# 1-Schematic_Esp12F.net
KiCad netlist of a schematic drawn in EasyEDA
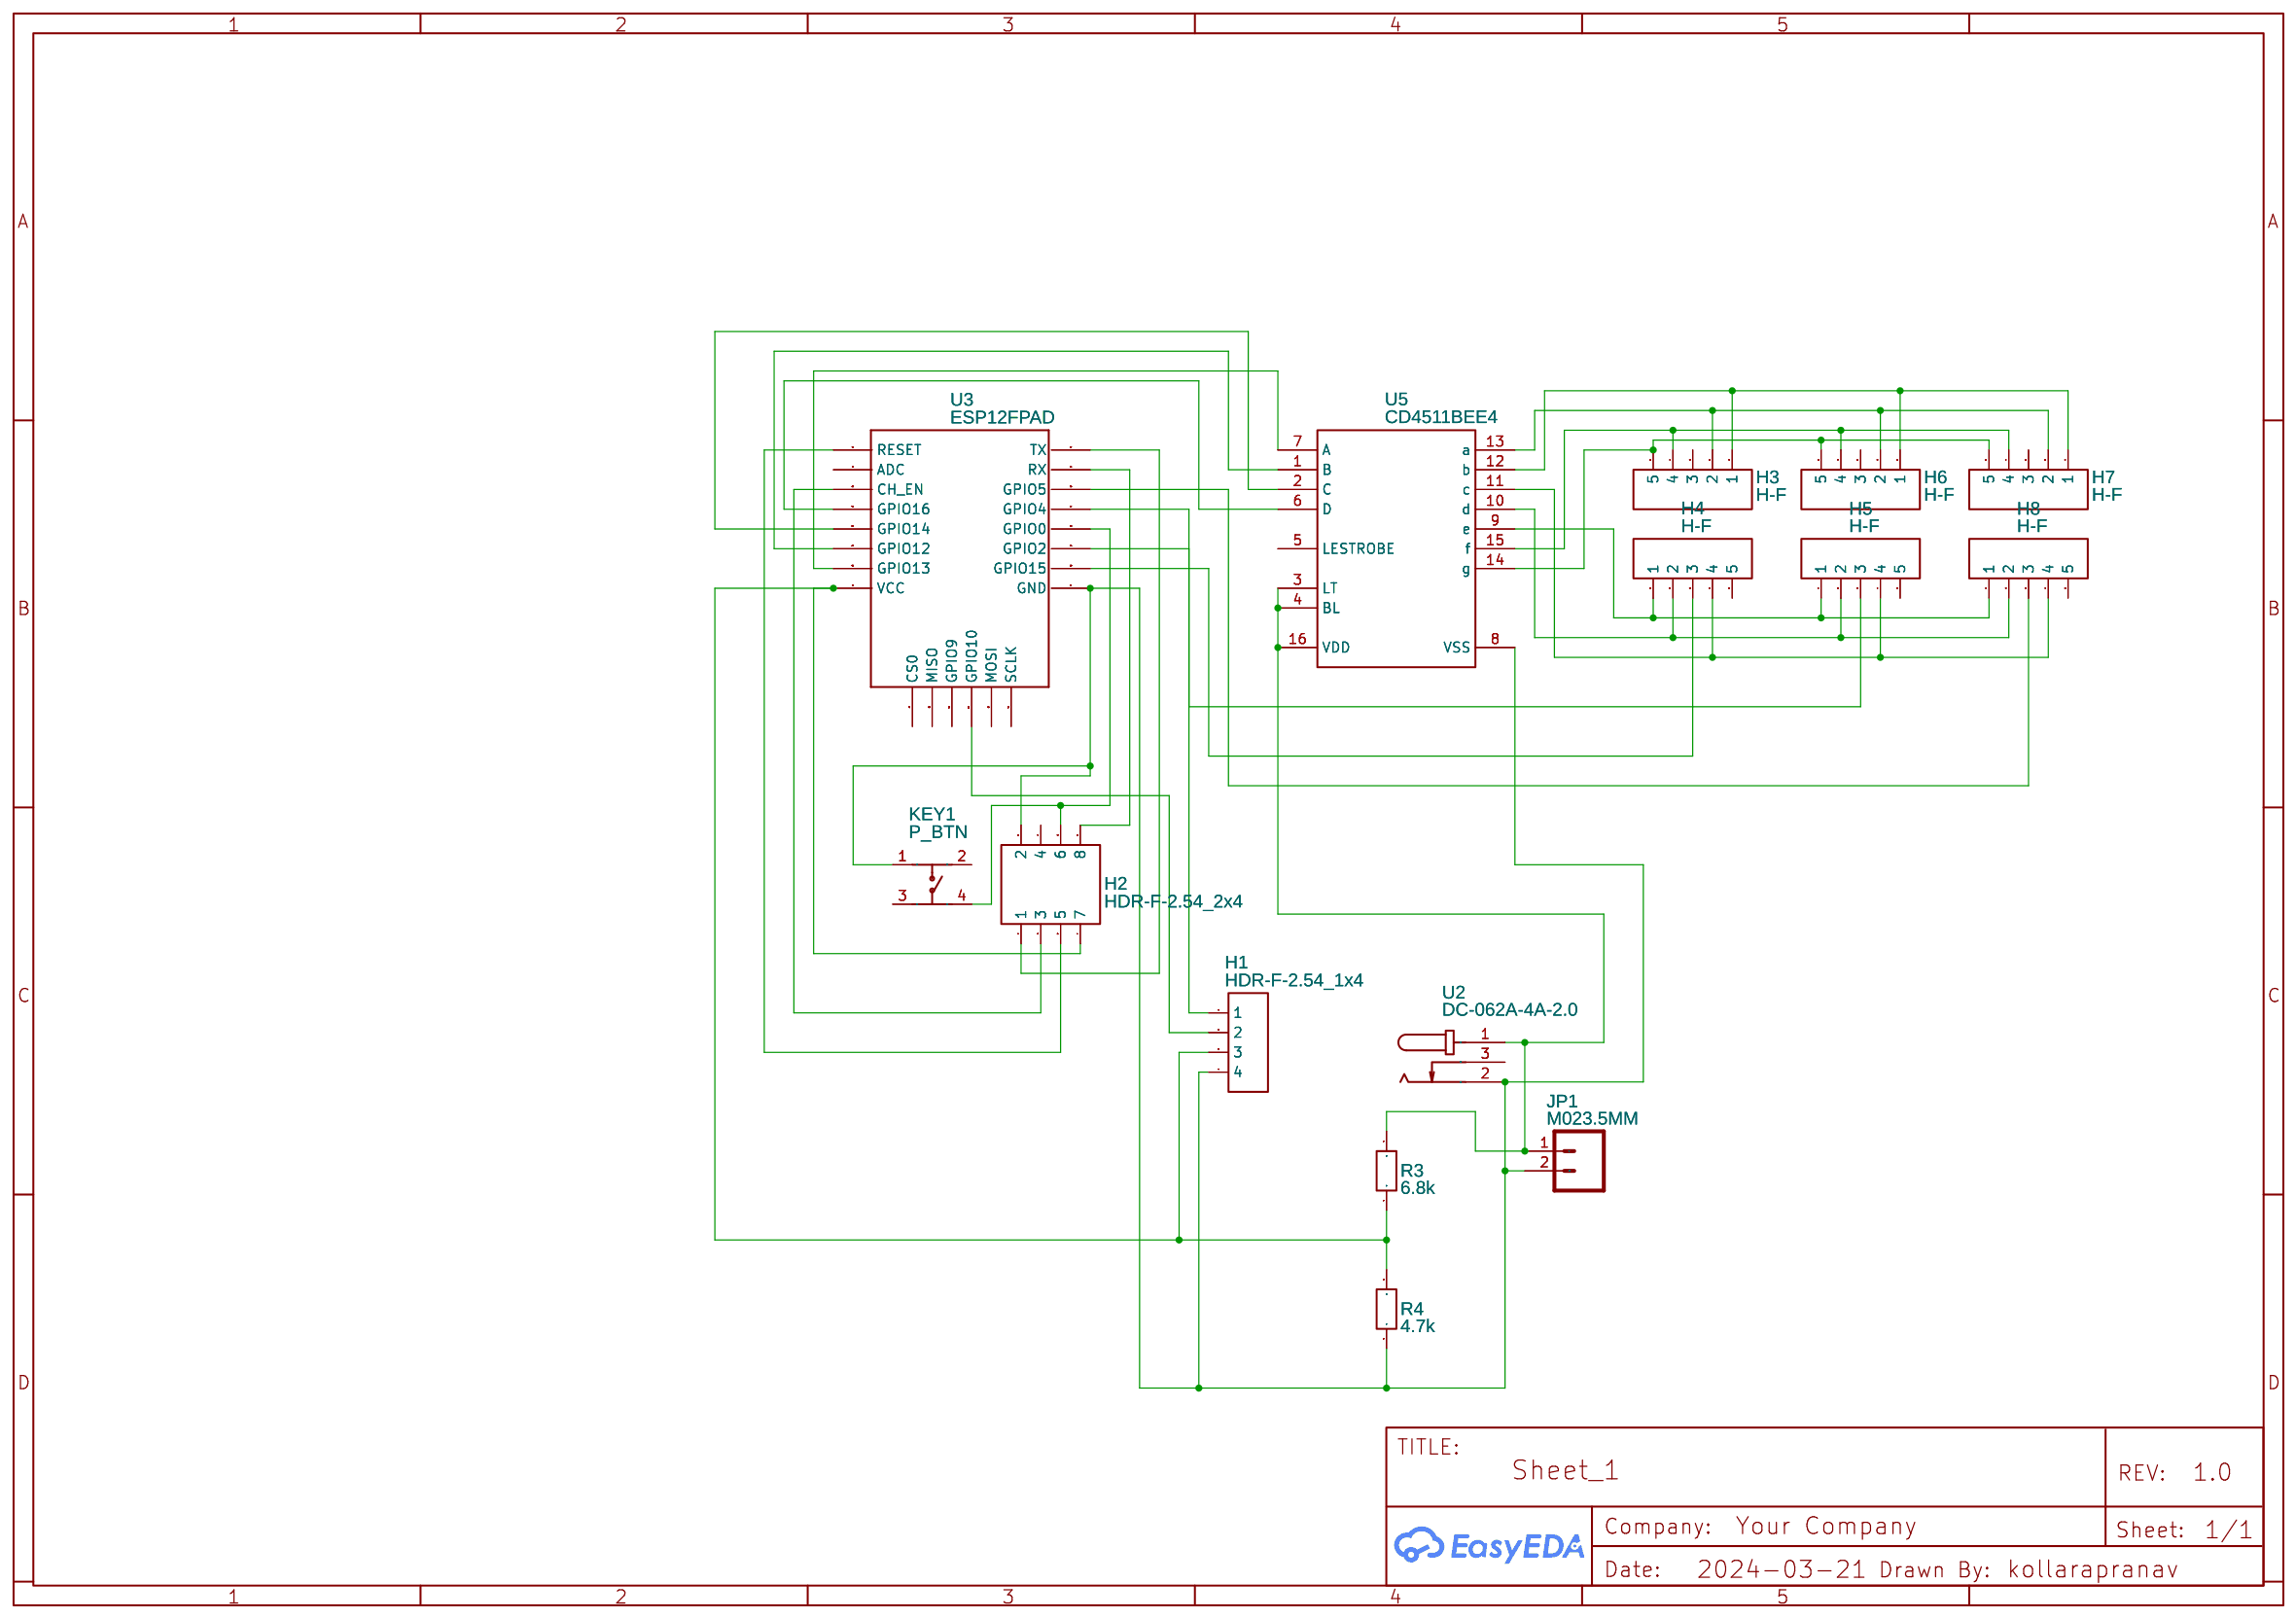
[diagram p0: schematic sheet]

(export (version "E")
  (design (tool "Eeschema 10.0.6"))
  (components
    (comp (ref "H1") (value "HDR-F-2.54_1x4") (libsource (lib "") (part "HDR-F-2.54_1x4")))
    (comp (ref "H2") (value "HDR-F-2.54_2x4") (libsource (lib "") (part "HDR-F-2.54_2x4")))
    (comp (ref "H3") (value "H-F") (libsource (lib "") (part "HDR-F-2.54_1x5")))
    (comp (ref "H4") (value "H-F") (libsource (lib "") (part "HDR-F-2.54_1x5_1")))
    (comp (ref "H5") (value "H-F") (libsource (lib "") (part "HDR-F-2.54_1x5_1")))
    (comp (ref "H6") (value "H-F") (libsource (lib "") (part "HDR-F-2.54_1x5")))
    (comp (ref "H7") (value "H-F") (libsource (lib "") (part "HDR-F-2.54_1x5")))
    (comp (ref "H8") (value "H-F") (libsource (lib "") (part "HDR-F-2.54_1x5_1")))
    (comp (ref "JP1") (value "M023.5MM") (libsource (lib "") (part "M023.5MM")))
    (comp (ref "KEY1")
      (value "P_BTN")
      (fields (field (name "Manufacturer Part") "4pinTACTPCBTHTPushButton"))
      (libsource (lib "") (part "4PINTACTPCBTHTPUSHBUTTON"))
    )
    (comp (ref "R3") (value "6.8k") (libsource (lib "") (part "Res_AXIAL-0.4(1/4W)_EU")))
    (comp (ref "R4") (value "4.7k") (libsource (lib "") (part "Res_AXIAL-0.4(1/4W)_EU")))
    (comp (ref "U2")
      (value "DC-062A-4A-2.0")
      (fields (field (name "Manufacturer") "XKB Connection(中国星坤)"))
      (libsource (lib "") (part "DC-062A-4A-2.0"))
    )
    (comp (ref "U3") (value "ESP12FPAD") (libsource (lib "") (part "ESP12FPAD")))
    (comp (ref "U5") (value "CD4511BEE4") (libsource (lib "") (part "CD4511BEE4")))
  )
  (nets
    (net (code "1") (name "Net-(H1-Pad1)") (class "Default")
      (node (ref "H1") (pin "1") (pinfunction "1_1") (pintype "unspecified"))
      (node (ref "U3") (pin "GPIO4") (pinfunction "GPIO4_GPIO4") (pintype "bidirectional"))
    )
    (net (code "2") (name "Net-(H1-Pad2)") (class "Default")
      (node (ref "H1") (pin "2") (pinfunction "2_2") (pintype "unspecified"))
      (node (ref "U3") (pin "GPIO10") (pinfunction "GPIO10_GPIO10") (pintype "bidirectional"))
    )
    (net (code "3") (name "Net-(H1-Pad3)") (class "Default")
      (node (ref "H1") (pin "3") (pinfunction "3_3") (pintype "unspecified"))
      (node (ref "H2") (pin "7") (pinfunction "7_7") (pintype "unspecified"))
      (node (ref "R3") (pin "1") (pinfunction "1_1") (pintype "unspecified"))
      (node (ref "R4") (pin "2") (pinfunction "2_2") (pintype "unspecified"))
      (node (ref "U3") (pin "VCC") (pinfunction "VCC_VCC") (pintype "bidirectional"))
    )
    (net (code "4") (name "Net-(H2-Pad5)") (class "Default")
      (node (ref "H2") (pin "5") (pinfunction "5_5") (pintype "unspecified"))
      (node (ref "U3") (pin "RESET") (pinfunction "RESET_RESET") (pintype "bidirectional"))
    )
    (net (code "5") (name "Net-(H2-Pad6)") (class "Default")
      (node (ref "H2") (pin "6") (pinfunction "6_6") (pintype "unspecified"))
      (node (ref "KEY1") (pin "4") (pinfunction "4_4") (pintype "unspecified"))
      (node (ref "U3") (pin "GPIO0") (pinfunction "GPIO0_GPIO0") (pintype "bidirectional"))
    )
    (net (code "6") (name "Net-(H4-Pad3)") (class "Default")
      (node (ref "H4") (pin "3") (pinfunction "3_3") (pintype "unspecified"))
      (node (ref "U3") (pin "GPIO15") (pinfunction "GPIO15_GPIO15") (pintype "bidirectional"))
    )
    (net (code "7") (name "Net-(H5-Pad3)") (class "Default")
      (node (ref "H5") (pin "3") (pinfunction "3_3") (pintype "unspecified"))
      (node (ref "U3") (pin "GPIO2") (pinfunction "GPIO2_GPIO2") (pintype "bidirectional"))
    )
    (net (code "8") (name "Net-(H8-Pad3)") (class "Default")
      (node (ref "H8") (pin "3") (pinfunction "3_3") (pintype "unspecified"))
      (node (ref "U3") (pin "GPIO5") (pinfunction "GPIO5_GPIO5") (pintype "bidirectional"))
    )
    (net (code "9") (name "Net-(U3-CH_EN)") (class "Default")
      (node (ref "H2") (pin "3") (pinfunction "3_3") (pintype "unspecified"))
      (node (ref "U3") (pin "CH_PD") (pinfunction "CH_EN_CH_PD") (pintype "bidirectional"))
    )
    (net (code "10") (name "Net-(U3-RX)") (class "Default")
      (node (ref "H2") (pin "8") (pinfunction "8_8") (pintype "unspecified"))
      (node (ref "U3") (pin "RXD0") (pinfunction "RX_RXD0") (pintype "bidirectional"))
    )
    (net (code "11") (name "Net-(U3-TX)") (class "Default")
      (node (ref "H2") (pin "1") (pinfunction "1_1") (pintype "unspecified"))
      (node (ref "U3") (pin "TXD0") (pinfunction "TX_TXD0") (pintype "bidirectional"))
    )
    (net (code "12") (name "Net-(U5-A)") (class "Default")
      (node (ref "U3") (pin "GPIO13") (pinfunction "GPIO13_GPIO13") (pintype "bidirectional"))
      (node (ref "U5") (pin "7") (pinfunction "A_7") (pintype "unspecified"))
    )
    (net (code "13") (name "Net-(U5-B)") (class "Default")
      (node (ref "U3") (pin "GPIO12") (pinfunction "GPIO12_GPIO12") (pintype "bidirectional"))
      (node (ref "U5") (pin "1") (pinfunction "B_1") (pintype "unspecified"))
    )
    (net (code "14") (name "Net-(U5-BL)") (class "Default")
      (node (ref "JP1") (pin "1") (pinfunction "1_1") (pintype "unspecified"))
      (node (ref "R3") (pin "2") (pinfunction "2_2") (pintype "unspecified"))
      (node (ref "U2") (pin "1") (pinfunction "1_1") (pintype "unspecified"))
      (node (ref "U5") (pin "16") (pinfunction "VDD_16") (pintype "passive"))
      (node (ref "U5") (pin "3") (pinfunction "LT_3") (pintype "unspecified"))
      (node (ref "U5") (pin "4") (pinfunction "BL_4") (pintype "unspecified"))
    )
    (net (code "15") (name "Net-(U5-C)") (class "Default")
      (node (ref "U3") (pin "GPIO14") (pinfunction "GPIO14_GPIO14") (pintype "bidirectional"))
      (node (ref "U5") (pin "2") (pinfunction "C_2") (pintype "unspecified"))
    )
    (net (code "16") (name "Net-(U5-D)") (class "Default")
      (node (ref "U3") (pin "GPIO16") (pinfunction "GPIO16_GPIO16") (pintype "bidirectional"))
      (node (ref "U5") (pin "6") (pinfunction "D_6") (pintype "unspecified"))
    )
    (net (code "17") (name "Net-(U5-VSS)") (class "Default")
      (node (ref "H1") (pin "4") (pinfunction "4_4") (pintype "unspecified"))
      (node (ref "H2") (pin "2") (pinfunction "2_2") (pintype "unspecified"))
      (node (ref "JP1") (pin "2") (pinfunction "2_2") (pintype "unspecified"))
      (node (ref "KEY1") (pin "1") (pinfunction "1_1") (pintype "unspecified"))
      (node (ref "R4") (pin "1") (pinfunction "1_1") (pintype "unspecified"))
      (node (ref "U2") (pin "2") (pinfunction "2_2") (pintype "unspecified"))
      (node (ref "U3") (pin "GND") (pinfunction "GND_GND") (pintype "bidirectional"))
      (node (ref "U5") (pin "8") (pinfunction "VSS_8") (pintype "passive"))
    )
    (net (code "18") (name "Net-(U5-a)") (class "Default")
      (node (ref "H3") (pin "2") (pinfunction "2_2") (pintype "unspecified"))
      (node (ref "H6") (pin "2") (pinfunction "2_2") (pintype "unspecified"))
      (node (ref "H7") (pin "2") (pinfunction "2_2") (pintype "unspecified"))
      (node (ref "U5") (pin "13") (pinfunction "a_13") (pintype "output"))
    )
    (net (code "19") (name "Net-(U5-b)") (class "Default")
      (node (ref "H3") (pin "1") (pinfunction "1_1") (pintype "unspecified"))
      (node (ref "H6") (pin "1") (pinfunction "1_1") (pintype "unspecified"))
      (node (ref "H7") (pin "1") (pinfunction "1_1") (pintype "unspecified"))
      (node (ref "U5") (pin "12") (pinfunction "b_12") (pintype "output"))
    )
    (net (code "20") (name "Net-(U5-c)") (class "Default")
      (node (ref "H4") (pin "4") (pinfunction "4_4") (pintype "unspecified"))
      (node (ref "H5") (pin "4") (pinfunction "4_4") (pintype "unspecified"))
      (node (ref "H8") (pin "4") (pinfunction "4_4") (pintype "unspecified"))
      (node (ref "U5") (pin "11") (pinfunction "c_11") (pintype "output"))
    )
    (net (code "21") (name "Net-(U5-d)") (class "Default")
      (node (ref "H4") (pin "2") (pinfunction "2_2") (pintype "unspecified"))
      (node (ref "H5") (pin "2") (pinfunction "2_2") (pintype "unspecified"))
      (node (ref "H8") (pin "2") (pinfunction "2_2") (pintype "unspecified"))
      (node (ref "U5") (pin "10") (pinfunction "d_10") (pintype "output"))
    )
    (net (code "22") (name "Net-(U5-e)") (class "Default")
      (node (ref "H4") (pin "1") (pinfunction "1_1") (pintype "unspecified"))
      (node (ref "H5") (pin "1") (pinfunction "1_1") (pintype "unspecified"))
      (node (ref "H8") (pin "1") (pinfunction "1_1") (pintype "unspecified"))
      (node (ref "U5") (pin "9") (pinfunction "e_9") (pintype "output"))
    )
    (net (code "23") (name "Net-(U5-f)") (class "Default")
      (node (ref "H3") (pin "4") (pinfunction "4_4") (pintype "unspecified"))
      (node (ref "H6") (pin "4") (pinfunction "4_4") (pintype "unspecified"))
      (node (ref "H7") (pin "4") (pinfunction "4_4") (pintype "unspecified"))
      (node (ref "U5") (pin "15") (pinfunction "f_15") (pintype "output"))
    )
    (net (code "24") (name "Net-(U5-g)") (class "Default")
      (node (ref "H3") (pin "5") (pinfunction "5_5") (pintype "unspecified"))
      (node (ref "H6") (pin "5") (pinfunction "5_5") (pintype "unspecified"))
      (node (ref "H7") (pin "5") (pinfunction "5_5") (pintype "unspecified"))
      (node (ref "U5") (pin "14") (pinfunction "g_14") (pintype "output"))
    )
    (net (code "25") (name "unconnected-(H2-Pad4)") (class "Default")
      (node (ref "H2") (pin "4") (pinfunction "4_4") (pintype "unspecified"))
    )
    (net (code "26") (name "unconnected-(H3-Pad3)") (class "Default")
      (node (ref "H3") (pin "3") (pinfunction "3_3") (pintype "unspecified"))
    )
    (net (code "27") (name "unconnected-(H4-Pad5)") (class "Default")
      (node (ref "H4") (pin "5") (pinfunction "5_5") (pintype "unspecified"))
    )
    (net (code "28") (name "unconnected-(H5-Pad5)") (class "Default")
      (node (ref "H5") (pin "5") (pinfunction "5_5") (pintype "unspecified"))
    )
    (net (code "29") (name "unconnected-(H6-Pad3)") (class "Default")
      (node (ref "H6") (pin "3") (pinfunction "3_3") (pintype "unspecified"))
    )
    (net (code "30") (name "unconnected-(H7-Pad3)") (class "Default")
      (node (ref "H7") (pin "3") (pinfunction "3_3") (pintype "unspecified"))
    )
    (net (code "31") (name "unconnected-(H8-Pad5)") (class "Default")
      (node (ref "H8") (pin "5") (pinfunction "5_5") (pintype "unspecified"))
    )
    (net (code "32") (name "unconnected-(KEY1-Pad2)") (class "Default")
      (node (ref "KEY1") (pin "2") (pinfunction "2_2") (pintype "unspecified"))
    )
    (net (code "33") (name "unconnected-(KEY1-Pad3)") (class "Default")
      (node (ref "KEY1") (pin "3") (pinfunction "3_3") (pintype "unspecified"))
    )
    (net (code "34") (name "unconnected-(U2-Pad3)") (class "Default")
      (node (ref "U2") (pin "3") (pinfunction "3_3") (pintype "unspecified"))
    )
    (net (code "35") (name "unconnected-(U3-PadADC)") (class "Default")
      (node (ref "U3") (pin "ADC") (pinfunction "ADC_ADC") (pintype "bidirectional"))
    )
    (net (code "36") (name "unconnected-(U3-PadCS0)") (class "Default")
      (node (ref "U3") (pin "CS0") (pinfunction "CS0_CS0") (pintype "bidirectional"))
    )
    (net (code "37") (name "unconnected-(U3-PadGPIO9)") (class "Default")
      (node (ref "U3") (pin "GPIO9") (pinfunction "GPIO9_GPIO9") (pintype "bidirectional"))
    )
    (net (code "38") (name "unconnected-(U3-PadMISO)") (class "Default")
      (node (ref "U3") (pin "MISO") (pinfunction "MISO_MISO") (pintype "bidirectional"))
    )
    (net (code "39") (name "unconnected-(U3-PadMOSI)") (class "Default")
      (node (ref "U3") (pin "MOSI") (pinfunction "MOSI_MOSI") (pintype "bidirectional"))
    )
    (net (code "40") (name "unconnected-(U3-PadSCLK)") (class "Default")
      (node (ref "U3") (pin "SCLK") (pinfunction "SCLK_SCLK") (pintype "bidirectional"))
    )
    (net (code "41") (name "unconnected-(U5-LESTROBE-Pad5)") (class "Default")
      (node (ref "U5") (pin "5") (pinfunction "LESTROBE_5") (pintype "unspecified"))
    )
  )
)
